# HDMI.net
KiCad netlist of a schematic drawn in Altium Designer
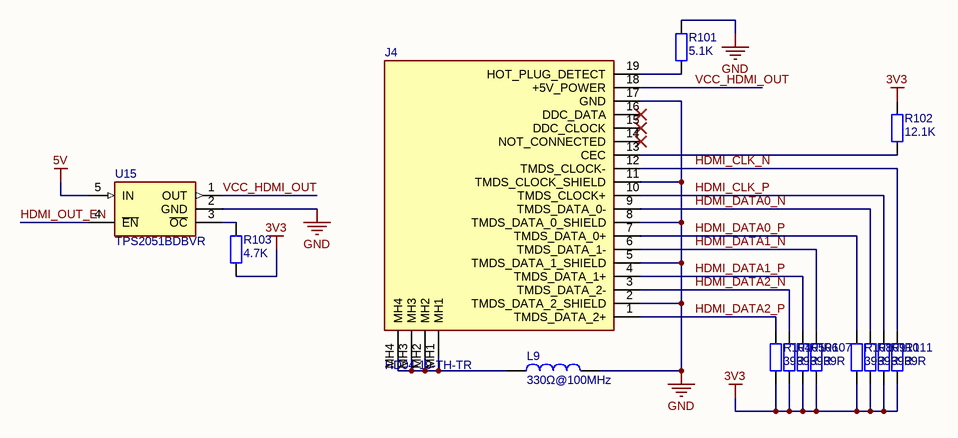
[diagram p0: HDMI.SchDoc]

(export (version "E")
  (design (tool "Eeschema 10.0.6"))
  (components
    (comp (ref "J4")
      (value "HD04-19-TH-TR")
      (footprint "HD0419THTR")
      (description "HDMI接口")
      (fields (field (name "MOUSER PART NUMBER") "179-HD04-19-TH-TR"))
      (libsource (lib "4.1   - 接口类") (part "HD04-19-TH-TR"))
    )
    (comp (ref "L9")
      (value "330Ω@100MHz")
      (footprint "L 0805")
      (description "小功率贴片电感")
      (fields (field (name "版权归属") "源创客"))
      (libsource (lib "3.1   - 电阻-电容-电感") (part "L"))
    )
    (comp (ref "R101")
      (value "5.1K")
      (footprint "R 0402_L")
      (description "贴片电阻")
      (fields (field (name "版权归属") "源创客"))
      (libsource (lib "3.1   - 电阻-电容-电感") (part "R"))
    )
    (comp (ref "R102")
      (value "12.1K")
      (footprint "R 0805_L")
      (description "贴片电阻")
      (fields (field (name "版权归属") "源创客"))
      (libsource (lib "3.1   - 电阻-电容-电感") (part "R"))
    )
    (comp (ref "R103")
      (value "4.7K")
      (footprint "R 0402_L")
      (description "贴片电阻")
      (fields (field (name "版权归属") "源创客"))
      (libsource (lib "3.1   - 电阻-电容-电感") (part "R"))
    )
    (comp (ref "R104")
      (value "39R")
      (footprint "R 0805_L")
      (description "贴片电阻")
      (fields (field (name "版权归属") "源创客"))
      (libsource (lib "3.1   - 电阻-电容-电感") (part "R"))
    )
    (comp (ref "R105")
      (value "39R")
      (footprint "R 0805_L")
      (description "贴片电阻")
      (fields (field (name "版权归属") "源创客"))
      (libsource (lib "3.1   - 电阻-电容-电感") (part "R"))
    )
    (comp (ref "R106")
      (value "39R")
      (footprint "R 0805_L")
      (description "贴片电阻")
      (fields (field (name "版权归属") "源创客"))
      (libsource (lib "3.1   - 电阻-电容-电感") (part "R"))
    )
    (comp (ref "R107")
      (value "39R")
      (footprint "R 0805_L")
      (description "贴片电阻")
      (fields (field (name "版权归属") "源创客"))
      (libsource (lib "3.1   - 电阻-电容-电感") (part "R"))
    )
    (comp (ref "R108")
      (value "39R")
      (footprint "R 0805_L")
      (description "贴片电阻")
      (fields (field (name "版权归属") "源创客"))
      (libsource (lib "3.1   - 电阻-电容-电感") (part "R"))
    )
    (comp (ref "R109")
      (value "39R")
      (footprint "R 0805_L")
      (description "贴片电阻")
      (fields (field (name "版权归属") "源创客"))
      (libsource (lib "3.1   - 电阻-电容-电感") (part "R"))
    )
    (comp (ref "R110")
      (value "39R")
      (footprint "R 0805_L")
      (description "贴片电阻")
      (fields (field (name "版权归属") "源创客"))
      (libsource (lib "3.1   - 电阻-电容-电感") (part "R"))
    )
    (comp (ref "R111")
      (value "39R")
      (footprint "R 0805_L")
      (description "贴片电阻")
      (fields (field (name "版权归属") "源创客"))
      (libsource (lib "3.1   - 电阻-电容-电感") (part "R"))
    )
    (comp (ref "U15")
      (value "TPS2051BDBVR")
      (footprint "SOT23-5N")
      (description "模拟开关芯片")
      (fields (field (name "MOUSER PART NUMBER") "595-TPS2051BDBVR"))
      (libsource (lib "1.1   - IC芯片") (part "TPS2051BDBVR"))
    )
  )
  (nets
    (net (code "1") (name "/HDMI_CLK_N") (class "Default")
      (node (ref "J4") (pin "12") (pinfunction "TMDS_CLOCK-_12") (pintype "passive"))
      (node (ref "R111") (pin "1") (pinfunction "1_1") (pintype "passive"))
    )
    (net (code "2") (name "/HDMI_CLK_P") (class "Default")
      (node (ref "J4") (pin "10") (pinfunction "TMDS_CLOCK+_10") (pintype "passive"))
      (node (ref "R110") (pin "1") (pinfunction "1_1") (pintype "passive"))
    )
    (net (code "3") (name "/HDMI_DATA0_N") (class "Default")
      (node (ref "J4") (pin "9") (pinfunction "TMDS_DATA_0-_9") (pintype "passive"))
      (node (ref "R109") (pin "1") (pinfunction "1_1") (pintype "passive"))
    )
    (net (code "4") (name "/HDMI_DATA0_P") (class "Default")
      (node (ref "J4") (pin "7") (pinfunction "TMDS_DATA_0+_7") (pintype "passive"))
      (node (ref "R108") (pin "1") (pinfunction "1_1") (pintype "passive"))
    )
    (net (code "5") (name "/HDMI_DATA1_N") (class "Default")
      (node (ref "J4") (pin "6") (pinfunction "TMDS_DATA_1-_6") (pintype "passive"))
      (node (ref "R107") (pin "1") (pinfunction "1_1") (pintype "passive"))
    )
    (net (code "6") (name "/HDMI_DATA1_P") (class "Default")
      (node (ref "J4") (pin "4") (pinfunction "TMDS_DATA_1+_4") (pintype "passive"))
      (node (ref "R106") (pin "1") (pinfunction "1_1") (pintype "passive"))
    )
    (net (code "7") (name "/HDMI_DATA2_N") (class "Default")
      (node (ref "J4") (pin "3") (pinfunction "TMDS_DATA_2-_3") (pintype "passive"))
      (node (ref "R105") (pin "1") (pinfunction "1_1") (pintype "passive"))
    )
    (net (code "8") (name "/HDMI_DATA2_P") (class "Default")
      (node (ref "J4") (pin "1") (pinfunction "TMDS_DATA_2+_1") (pintype "passive"))
      (node (ref "R104") (pin "1") (pinfunction "1_1") (pintype "passive"))
    )
    (net (code "9") (name "/HDMI_OUT_EN") (class "Default")
      (node (ref "U15") (pin "4") (pinfunction "~{EN}_4") (pintype "passive"))
    )
    (net (code "10") (name "/VCC_HDMI_OUT") (class "Default")
      (node (ref "J4") (pin "18") (pinfunction "+5V_POWER_18") (pintype "passive"))
      (node (ref "U15") (pin "1") (pinfunction "OUT_1") (pintype "output"))
    )
    (net (code "11") (name "3V3") (class "Default")
      (node (ref "R102") (pin "1") (pinfunction "1_1") (pintype "passive"))
      (node (ref "R103") (pin "1") (pinfunction "1_1") (pintype "passive"))
      (node (ref "R104") (pin "2") (pinfunction "2_2") (pintype "passive"))
      (node (ref "R105") (pin "2") (pinfunction "2_2") (pintype "passive"))
      (node (ref "R106") (pin "2") (pinfunction "2_2") (pintype "passive"))
      (node (ref "R107") (pin "2") (pinfunction "2_2") (pintype "passive"))
      (node (ref "R108") (pin "2") (pinfunction "2_2") (pintype "passive"))
      (node (ref "R109") (pin "2") (pinfunction "2_2") (pintype "passive"))
      (node (ref "R110") (pin "2") (pinfunction "2_2") (pintype "passive"))
      (node (ref "R111") (pin "2") (pinfunction "2_2") (pintype "passive"))
    )
    (net (code "12") (name "5V") (class "Default")
      (node (ref "U15") (pin "5") (pinfunction "IN_5") (pintype "input"))
    )
    (net (code "13") (name "GND") (class "Default")
      (node (ref "J4") (pin "11") (pinfunction "TMDS_CLOCK_SHIELD_11") (pintype "passive"))
      (node (ref "J4") (pin "17") (pinfunction "GND_17") (pintype "passive"))
      (node (ref "J4") (pin "2") (pinfunction "TMDS_DATA_2_SHIELD_2") (pintype "passive"))
      (node (ref "J4") (pin "5") (pinfunction "TMDS_DATA_1_SHIELD_5") (pintype "passive"))
      (node (ref "J4") (pin "8") (pinfunction "TMDS_DATA_0_SHIELD_8") (pintype "passive"))
      (node (ref "L9") (pin "2") (pinfunction "2_2") (pintype "passive"))
      (node (ref "R101") (pin "1") (pinfunction "1_1") (pintype "passive"))
      (node (ref "U15") (pin "2") (pinfunction "GND_2") (pintype "power_in"))
    )
    (net (code "14") (name "Net-(J4-CEC)") (class "Default")
      (node (ref "J4") (pin "13") (pinfunction "CEC_13") (pintype "passive"))
      (node (ref "R102") (pin "2") (pinfunction "2_2") (pintype "passive"))
    )
    (net (code "15") (name "Net-(J4-HOT_PLUG_DETECT)") (class "Default")
      (node (ref "J4") (pin "19") (pinfunction "HOT_PLUG_DETECT_19") (pintype "passive"))
      (node (ref "R101") (pin "2") (pinfunction "2_2") (pintype "passive"))
    )
    (net (code "16") (name "Net-(J4-PadMH1)") (class "Default")
      (node (ref "J4") (pin "MH1") (pinfunction "MH1_MH1") (pintype "passive"))
      (node (ref "J4") (pin "MH2") (pinfunction "MH2_MH2") (pintype "passive"))
      (node (ref "J4") (pin "MH3") (pinfunction "MH3_MH3") (pintype "passive"))
      (node (ref "J4") (pin "MH4") (pinfunction "MH4_MH4") (pintype "passive"))
      (node (ref "L9") (pin "1") (pinfunction "1_1") (pintype "passive"))
    )
    (net (code "17") (name "Net-(U15-~{OC})") (class "Default")
      (node (ref "R103") (pin "2") (pinfunction "2_2") (pintype "passive"))
      (node (ref "U15") (pin "3") (pinfunction "~{OC}_3") (pintype "passive"))
    )
    (net (code "18") (name "unconnected-(J4-DDC_CLOCK-Pad15)") (class "Default")
      (node (ref "J4") (pin "15") (pinfunction "DDC_CLOCK_15") (pintype "passive+no_connect"))
    )
    (net (code "19") (name "unconnected-(J4-DDC_DATA-Pad16)") (class "Default")
      (node (ref "J4") (pin "16") (pinfunction "DDC_DATA_16") (pintype "passive+no_connect"))
    )
    (net (code "20") (name "unconnected-(J4-NOT_CONNECTED-Pad14)") (class "Default")
      (node (ref "J4") (pin "14") (pinfunction "NOT_CONNECTED_14") (pintype "passive+no_connect"))
    )
  )
)
